# PCB-ETHMG-BOS2_v05-16.net
KiCad netlist of a schematic drawn in EAGLE
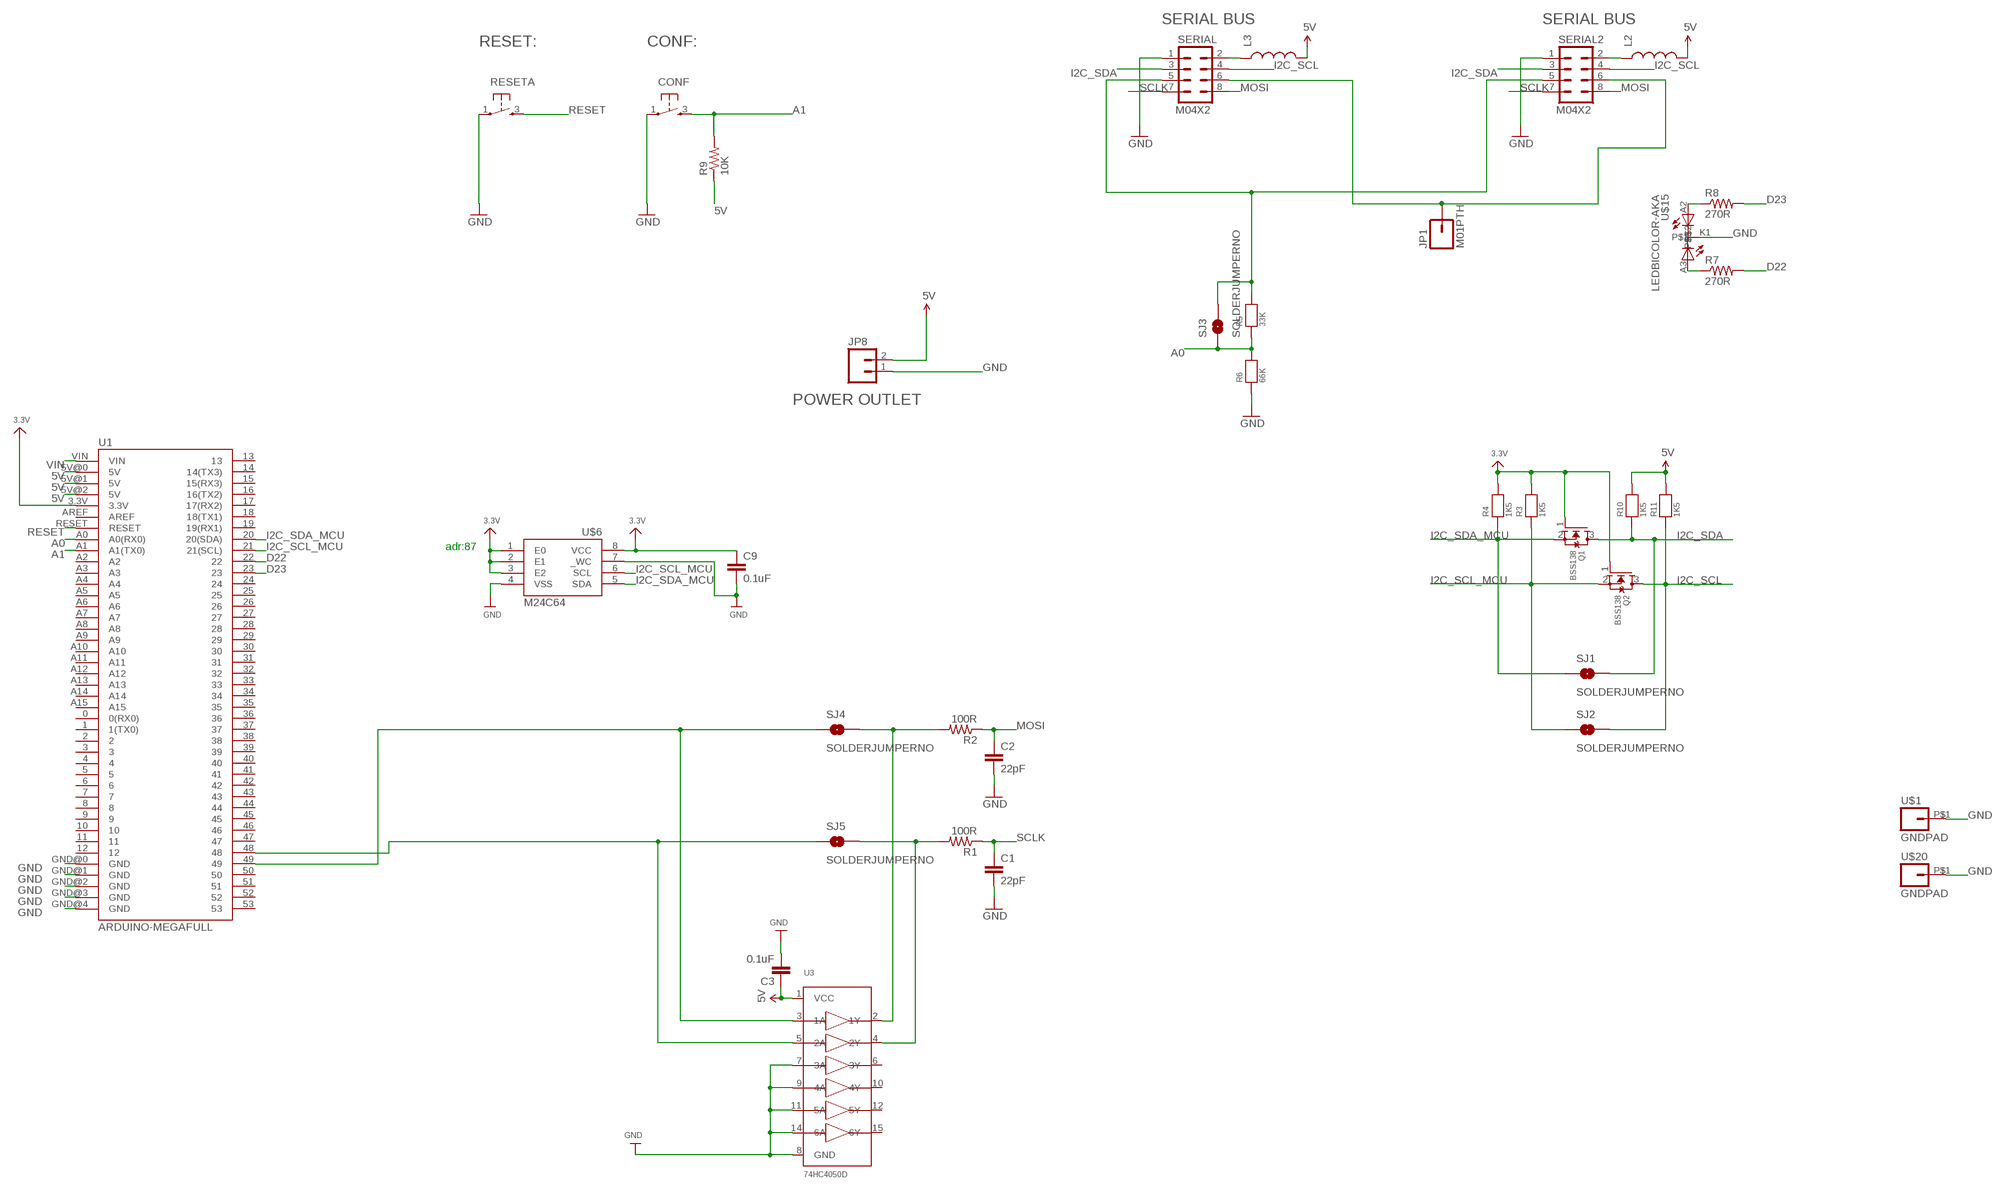
[diagram p0: schematic, sheet 1]

(export (version "E")
  (design (tool "Eeschema 10.0.6"))
  (components
    (comp (ref "C1")
      (value "22pF")
      (footprint "eagle-import:0603-CAP")
      (libsource (lib "eagle-import") (part "CAP0603-CAP"))
    )
    (comp (ref "C2")
      (value "22pF")
      (footprint "eagle-import:0603-CAP")
      (libsource (lib "eagle-import") (part "CAP0603-CAP"))
    )
    (comp (ref "C3")
      (value "0.1uF")
      (footprint "eagle-import:0603-CAP")
      (libsource (lib "eagle-import") (part "CAP0603-CAP"))
    )
    (comp (ref "C9")
      (value "0.1uF")
      (footprint "eagle-import:0603-CAP")
      (libsource (lib "eagle-import") (part "CAP0603-CAP"))
    )
    (comp (ref "CONF")
      (value "TAC_SWITCH")
      (footprint "eagle-import:PUSHBUTTON")
      (libsource (lib "eagle-import") (part "TAC_SWITCH"))
    )
    (comp (ref "JP1")
      (value "M01PTH")
      (footprint "eagle-import:1X01")
      (libsource (lib "eagle-import") (part "M01PTH"))
    )
    (comp (ref "JP8")
      (value "M02PTH4")
      (footprint "eagle-import:1X02_XTRA_BIG")
      (libsource (lib "eagle-import") (part "M02PTH4"))
    )
    (comp (ref "L2")
      (value "INDUCTOR0805")
      (footprint "eagle-import:0805")
      (libsource (lib "eagle-import") (part "INDUCTOR0805"))
    )
    (comp (ref "L3")
      (value "INDUCTOR0805")
      (footprint "eagle-import:0805")
      (libsource (lib "eagle-import") (part "INDUCTOR0805"))
    )
    (comp (ref "Q1")
      (value "BSS138")
      (footprint "eagle-import:SOT23-R")
      (libsource (lib "eagle-import") (part "MOSFET-NREFLOW"))
    )
    (comp (ref "Q2")
      (value "BSS138")
      (footprint "eagle-import:SOT23-R")
      (libsource (lib "eagle-import") (part "MOSFET-NREFLOW"))
    )
    (comp (ref "R1")
      (value "100R")
      (footprint "eagle-import:0603-RES")
      (libsource (lib "eagle-import") (part "RESISTOR0603-RES"))
    )
    (comp (ref "R2")
      (value "100R")
      (footprint "eagle-import:0603-RES")
      (libsource (lib "eagle-import") (part "RESISTOR0603-RES"))
    )
    (comp (ref "R3")
      (value "1K5")
      (footprint "eagle-import:0603")
      (libsource (lib "eagle-import") (part "RESISTOR0603"))
    )
    (comp (ref "R4")
      (value "1K5")
      (footprint "eagle-import:0603")
      (libsource (lib "eagle-import") (part "RESISTOR0603"))
    )
    (comp (ref "R5")
      (value "33K")
      (footprint "eagle-import:0603")
      (libsource (lib "eagle-import") (part "RESISTOR0603"))
    )
    (comp (ref "R6")
      (value "66K")
      (footprint "eagle-import:0603")
      (libsource (lib "eagle-import") (part "RESISTOR0603"))
    )
    (comp (ref "R7")
      (value "270R")
      (footprint "eagle-import:0603-RES")
      (libsource (lib "eagle-import") (part "RESISTOR0603-RES"))
    )
    (comp (ref "R8")
      (value "270R")
      (footprint "eagle-import:0603-RES")
      (libsource (lib "eagle-import") (part "RESISTOR0603-RES"))
    )
    (comp (ref "R9")
      (value "10K")
      (footprint "eagle-import:0603-RES")
      (libsource (lib "eagle-import") (part "RESISTOR0603-RES"))
    )
    (comp (ref "R10")
      (value "1K5")
      (footprint "eagle-import:0603")
      (libsource (lib "eagle-import") (part "RESISTOR0603"))
    )
    (comp (ref "R11")
      (value "1K5")
      (footprint "eagle-import:0603")
      (libsource (lib "eagle-import") (part "RESISTOR0603"))
    )
    (comp (ref "RESETA")
      (value "TAC_SWITCH")
      (footprint "eagle-import:PUSHBUTTON")
      (libsource (lib "eagle-import") (part "TAC_SWITCH"))
    )
    (comp (ref "SERIAL")
      (value "M04X2")
      (footprint "eagle-import:2X4")
      (libsource (lib "eagle-import") (part "M04X2"))
    )
    (comp (ref "SERIAL2")
      (value "M04X2")
      (footprint "eagle-import:2X4")
      (libsource (lib "eagle-import") (part "M04X2"))
    )
    (comp (ref "SJ1")
      (value "SOLDERJUMPERNO")
      (footprint "eagle-import:SJ_2S-NO")
      (libsource (lib "eagle-import") (part "SOLDERJUMPERNO"))
    )
    (comp (ref "SJ2")
      (value "SOLDERJUMPERNO")
      (footprint "eagle-import:SJ_2S-NO")
      (libsource (lib "eagle-import") (part "SOLDERJUMPERNO"))
    )
    (comp (ref "SJ3")
      (value "SOLDERJUMPERNO")
      (footprint "eagle-import:SJ_2S-NO")
      (libsource (lib "eagle-import") (part "SOLDERJUMPERNO"))
    )
    (comp (ref "SJ4")
      (value "SOLDERJUMPERNO")
      (footprint "eagle-import:SJ_2S-NO")
      (libsource (lib "eagle-import") (part "SOLDERJUMPERNO"))
    )
    (comp (ref "SJ5")
      (value "SOLDERJUMPERNO")
      (footprint "eagle-import:SJ_2S-NO")
      (libsource (lib "eagle-import") (part "SOLDERJUMPERNO"))
    )
    (comp (ref "U$1")
      (value "GNDPAD")
      (footprint "eagle-import:3.2MMPAD")
      (libsource (lib "eagle-import") (part "GNDPAD"))
    )
    (comp (ref "U$6")
      (value "M24C64")
      (footprint "eagle-import:TSSOP8")
      (libsource (lib "eagle-import") (part "M24C64"))
    )
    (comp (ref "U$15")
      (value "LEDBICOLOR-AKA")
      (footprint "eagle-import:LED5MM-BICOLOR")
      (libsource (lib "eagle-import") (part "LEDBICOLOR-AKA"))
    )
    (comp (ref "U$20")
      (value "GNDPAD")
      (footprint "eagle-import:3.2MMPAD")
      (libsource (lib "eagle-import") (part "GNDPAD"))
    )
    (comp (ref "U1")
      (value "ARDUINO-MEGAFULL")
      (footprint "eagle-import:ARDUINO_MEGA")
      (libsource (lib "eagle-import") (part "ARDUINO-MEGAFULL"))
    )
    (comp (ref "U3")
      (value "74HC4050D")
      (footprint "eagle-import:TSSOP16")
      (libsource (lib "eagle-import") (part "74HC4050DTSSOP16"))
    )
  )
  (nets
    (net (code "1") (name "/A0") (class "Default")
      (node (ref "R5") (pin "1") (pinfunction "1_1") (pintype "passive"))
      (node (ref "R6") (pin "2") (pinfunction "2_2") (pintype "passive"))
      (node (ref "SJ3") (pin "1") (pinfunction "1_1") (pintype "passive"))
      (node (ref "U1") (pin "A0") (pinfunction "A0(RX0)_A0") (pintype "bidirectional"))
    )
    (net (code "2") (name "/A1") (class "Default")
      (node (ref "CONF") (pin "3") (pinfunction "3_3") (pintype "passive"))
      (node (ref "R9") (pin "2") (pinfunction "2_2") (pintype "passive"))
      (node (ref "U1") (pin "A1") (pinfunction "A1(TX0)_A1") (pintype "bidirectional"))
    )
    (net (code "3") (name "/D22") (class "Default")
      (node (ref "R7") (pin "2") (pinfunction "2_2") (pintype "passive"))
      (node (ref "U1") (pin "22") (pinfunction "22_22") (pintype "bidirectional"))
    )
    (net (code "4") (name "/D23") (class "Default")
      (node (ref "R8") (pin "2") (pinfunction "2_2") (pintype "passive"))
      (node (ref "U1") (pin "23") (pinfunction "23_23") (pintype "bidirectional"))
    )
    (net (code "5") (name "/I2C_SCL") (class "Default")
      (node (ref "Q2") (pin "3") (pinfunction "D_3") (pintype "bidirectional"))
      (node (ref "R11") (pin "1") (pinfunction "1_1") (pintype "passive"))
      (node (ref "SERIAL") (pin "4") (pinfunction "4_4") (pintype "passive"))
      (node (ref "SERIAL2") (pin "4") (pinfunction "4_4") (pintype "passive"))
      (node (ref "SJ2") (pin "2") (pinfunction "2_2") (pintype "passive"))
    )
    (net (code "6") (name "/I2C_SCL_MCU") (class "Default")
      (node (ref "Q2") (pin "2") (pinfunction "S_2") (pintype "bidirectional"))
      (node (ref "R3") (pin "1") (pinfunction "1_1") (pintype "passive"))
      (node (ref "SJ2") (pin "1") (pinfunction "1_1") (pintype "passive"))
      (node (ref "U$6") (pin "6") (pinfunction "SCL_6") (pintype "bidirectional"))
      (node (ref "U1") (pin "21") (pinfunction "21(SCL)_21") (pintype "bidirectional"))
    )
    (net (code "7") (name "/I2C_SDA") (class "Default")
      (node (ref "Q1") (pin "3") (pinfunction "D_3") (pintype "bidirectional"))
      (node (ref "R10") (pin "1") (pinfunction "1_1") (pintype "passive"))
      (node (ref "SERIAL") (pin "3") (pinfunction "3_3") (pintype "passive"))
      (node (ref "SERIAL2") (pin "3") (pinfunction "3_3") (pintype "passive"))
      (node (ref "SJ1") (pin "2") (pinfunction "2_2") (pintype "passive"))
    )
    (net (code "8") (name "/I2C_SDA_MCU") (class "Default")
      (node (ref "Q1") (pin "2") (pinfunction "S_2") (pintype "bidirectional"))
      (node (ref "R4") (pin "1") (pinfunction "1_1") (pintype "passive"))
      (node (ref "SJ1") (pin "1") (pinfunction "1_1") (pintype "passive"))
      (node (ref "U$6") (pin "5") (pinfunction "SDA_5") (pintype "bidirectional"))
      (node (ref "U1") (pin "20") (pinfunction "20(SDA)_20") (pintype "bidirectional"))
    )
    (net (code "9") (name "/MOSI") (class "Default")
      (node (ref "C2") (pin "1") (pinfunction "1_1") (pintype "passive"))
      (node (ref "R2") (pin "1") (pinfunction "1_1") (pintype "passive"))
      (node (ref "SERIAL") (pin "8") (pinfunction "8_8") (pintype "passive"))
      (node (ref "SERIAL2") (pin "8") (pinfunction "8_8") (pintype "passive"))
    )
    (net (code "10") (name "/RESET") (class "Default")
      (node (ref "RESETA") (pin "3") (pinfunction "3_3") (pintype "passive"))
      (node (ref "U1") (pin "RESET") (pinfunction "RESET_RESET") (pintype "bidirectional"))
    )
    (net (code "11") (name "/SCLK") (class "Default")
      (node (ref "C1") (pin "1") (pinfunction "1_1") (pintype "passive"))
      (node (ref "R1") (pin "1") (pinfunction "1_1") (pintype "passive"))
      (node (ref "SERIAL") (pin "7") (pinfunction "7_7") (pintype "passive"))
      (node (ref "SERIAL2") (pin "7") (pinfunction "7_7") (pintype "passive"))
    )
    (net (code "12") (name "/VIN") (class "Default")
      (node (ref "U1") (pin "VIN") (pinfunction "VIN_VIN") (pintype "bidirectional"))
    )
    (net (code "13") (name "3.3V") (class "Default")
      (node (ref "C9") (pin "1") (pinfunction "1_1") (pintype "passive"))
      (node (ref "Q1") (pin "1") (pinfunction "G_1") (pintype "bidirectional"))
      (node (ref "Q2") (pin "1") (pinfunction "G_1") (pintype "bidirectional"))
      (node (ref "R3") (pin "2") (pinfunction "2_2") (pintype "passive"))
      (node (ref "R4") (pin "2") (pinfunction "2_2") (pintype "passive"))
      (node (ref "U$6") (pin "1") (pinfunction "E0_1") (pintype "bidirectional"))
      (node (ref "U$6") (pin "2") (pinfunction "E1_2") (pintype "bidirectional"))
      (node (ref "U$6") (pin "3") (pinfunction "E2_3") (pintype "bidirectional"))
      (node (ref "U$6") (pin "8") (pinfunction "VCC_8") (pintype "power_in"))
      (node (ref "U1") (pin "3.3V") (pinfunction "3.3V_3.3V") (pintype "bidirectional"))
    )
    (net (code "14") (name "5V") (class "Default")
      (node (ref "C3") (pin "1") (pinfunction "1_1") (pintype "passive"))
      (node (ref "JP8") (pin "2") (pinfunction "2_2") (pintype "passive"))
      (node (ref "L2") (pin "2") (pinfunction "2_2") (pintype "passive"))
      (node (ref "L3") (pin "2") (pinfunction "2_2") (pintype "passive"))
      (node (ref "R10") (pin "2") (pinfunction "2_2") (pintype "passive"))
      (node (ref "R11") (pin "2") (pinfunction "2_2") (pintype "passive"))
      (node (ref "R9") (pin "1") (pinfunction "1_1") (pintype "passive"))
      (node (ref "U1") (pin "5V@0") (pinfunction "5V_5V@0") (pintype "bidirectional"))
      (node (ref "U1") (pin "5V@1") (pinfunction "5V_5V@1") (pintype "bidirectional"))
      (node (ref "U1") (pin "5V@2") (pinfunction "5V_5V@2") (pintype "bidirectional"))
      (node (ref "U3") (pin "1") (pinfunction "VCC_1") (pintype "bidirectional"))
    )
    (net (code "15") (name "GND") (class "Default")
      (node (ref "C1") (pin "2") (pinfunction "2_2") (pintype "passive"))
      (node (ref "C2") (pin "2") (pinfunction "2_2") (pintype "passive"))
      (node (ref "C3") (pin "2") (pinfunction "2_2") (pintype "passive"))
      (node (ref "C9") (pin "2") (pinfunction "2_2") (pintype "passive"))
      (node (ref "CONF") (pin "1") (pinfunction "1_1") (pintype "passive"))
      (node (ref "JP8") (pin "1") (pinfunction "1_1") (pintype "passive"))
      (node (ref "R6") (pin "1") (pinfunction "1_1") (pintype "passive"))
      (node (ref "RESETA") (pin "1") (pinfunction "1_1") (pintype "passive"))
      (node (ref "SERIAL") (pin "1") (pinfunction "1_1") (pintype "passive"))
      (node (ref "SERIAL2") (pin "1") (pinfunction "1_1") (pintype "passive"))
      (node (ref "U$1") (pin "P$1") (pinfunction "1_P$1") (pintype "passive"))
      (node (ref "U$15") (pin "K1") (pinfunction "P$1_K1") (pintype "bidirectional"))
      (node (ref "U$20") (pin "P$1") (pinfunction "1_P$1") (pintype "passive"))
      (node (ref "U$6") (pin "4") (pinfunction "VSS_4") (pintype "power_in"))
      (node (ref "U$6") (pin "7") (pinfunction "_WC_7") (pintype "bidirectional"))
      (node (ref "U1") (pin "GND@0") (pinfunction "GND_GND@0") (pintype "bidirectional"))
      (node (ref "U1") (pin "GND@1") (pinfunction "GND_GND@1") (pintype "bidirectional"))
      (node (ref "U1") (pin "GND@2") (pinfunction "GND_GND@2") (pintype "bidirectional"))
      (node (ref "U1") (pin "GND@3") (pinfunction "GND_GND@3") (pintype "bidirectional"))
      (node (ref "U1") (pin "GND@4") (pinfunction "GND_GND@4") (pintype "bidirectional"))
      (node (ref "U3") (pin "11") (pinfunction "5A_11") (pintype "bidirectional"))
      (node (ref "U3") (pin "14") (pinfunction "6A_14") (pintype "bidirectional"))
      (node (ref "U3") (pin "7") (pinfunction "3A_7") (pintype "bidirectional"))
      (node (ref "U3") (pin "8") (pinfunction "GND_8") (pintype "bidirectional"))
      (node (ref "U3") (pin "9") (pinfunction "4A_9") (pintype "bidirectional"))
    )
    (net (code "16") (name "Net-(JP1-Pad1)") (class "Default")
      (node (ref "JP1") (pin "1") (pinfunction "1_1") (pintype "passive"))
      (node (ref "SERIAL") (pin "6") (pinfunction "6_6") (pintype "passive"))
      (node (ref "SERIAL2") (pin "6") (pinfunction "6_6") (pintype "passive"))
    )
    (net (code "17") (name "Net-(L2-Pad1)") (class "Default")
      (node (ref "L2") (pin "1") (pinfunction "1_1") (pintype "passive"))
      (node (ref "SERIAL2") (pin "2") (pinfunction "2_2") (pintype "passive"))
    )
    (net (code "18") (name "Net-(L3-Pad1)") (class "Default")
      (node (ref "L3") (pin "1") (pinfunction "1_1") (pintype "passive"))
      (node (ref "SERIAL") (pin "2") (pinfunction "2_2") (pintype "passive"))
    )
    (net (code "19") (name "Net-(R5-Pad2)") (class "Default")
      (node (ref "R5") (pin "2") (pinfunction "2_2") (pintype "passive"))
      (node (ref "SERIAL") (pin "5") (pinfunction "5_5") (pintype "passive"))
      (node (ref "SERIAL2") (pin "5") (pinfunction "5_5") (pintype "passive"))
      (node (ref "SJ3") (pin "2") (pinfunction "2_2") (pintype "passive"))
    )
    (net (code "20") (name "Net-(U$15-P$2)") (class "Default")
      (node (ref "R8") (pin "1") (pinfunction "1_1") (pintype "passive"))
      (node (ref "U$15") (pin "A2") (pinfunction "P$2_A2") (pintype "bidirectional"))
    )
    (net (code "21") (name "Net-(U$15-P$3)") (class "Default")
      (node (ref "R7") (pin "1") (pinfunction "1_1") (pintype "passive"))
      (node (ref "U$15") (pin "A3") (pinfunction "P$3_A3") (pintype "bidirectional"))
    )
    (net (code "22") (name "Net-(U3-1A)") (class "Default")
      (node (ref "SJ4") (pin "1") (pinfunction "1_1") (pintype "passive"))
      (node (ref "U1") (pin "49") (pinfunction "49_49") (pintype "bidirectional"))
      (node (ref "U3") (pin "3") (pinfunction "1A_3") (pintype "bidirectional"))
    )
    (net (code "23") (name "Net-(U3-1Y)") (class "Default")
      (node (ref "R2") (pin "2") (pinfunction "2_2") (pintype "passive"))
      (node (ref "SJ4") (pin "2") (pinfunction "2_2") (pintype "passive"))
      (node (ref "U3") (pin "2") (pinfunction "1Y_2") (pintype "bidirectional"))
    )
    (net (code "24") (name "Net-(U3-2A)") (class "Default")
      (node (ref "SJ5") (pin "1") (pinfunction "1_1") (pintype "passive"))
      (node (ref "U1") (pin "48") (pinfunction "48_48") (pintype "bidirectional"))
      (node (ref "U3") (pin "5") (pinfunction "2A_5") (pintype "bidirectional"))
    )
    (net (code "25") (name "Net-(U3-2Y)") (class "Default")
      (node (ref "R1") (pin "2") (pinfunction "2_2") (pintype "passive"))
      (node (ref "SJ5") (pin "2") (pinfunction "2_2") (pintype "passive"))
      (node (ref "U3") (pin "4") (pinfunction "2Y_4") (pintype "bidirectional"))
    )
    (net (code "26") (name "unconnected-(U1-0(RX0)-Pad0)") (class "Default")
      (node (ref "U1") (pin "0") (pinfunction "0(RX0)_0") (pintype "bidirectional"))
    )
    (net (code "27") (name "unconnected-(U1-1(TX0)-Pad1)") (class "Default")
      (node (ref "U1") (pin "1") (pinfunction "1(TX0)_1") (pintype "bidirectional"))
    )
    (net (code "28") (name "unconnected-(U1-14(TX3)-Pad14)") (class "Default")
      (node (ref "U1") (pin "14") (pinfunction "14(TX3)_14") (pintype "bidirectional"))
    )
    (net (code "29") (name "unconnected-(U1-15(RX3)-Pad15)") (class "Default")
      (node (ref "U1") (pin "15") (pinfunction "15(RX3)_15") (pintype "bidirectional"))
    )
    (net (code "30") (name "unconnected-(U1-16(TX2)-Pad16)") (class "Default")
      (node (ref "U1") (pin "16") (pinfunction "16(TX2)_16") (pintype "bidirectional"))
    )
    (net (code "31") (name "unconnected-(U1-17(RX2)-Pad17)") (class "Default")
      (node (ref "U1") (pin "17") (pinfunction "17(RX2)_17") (pintype "bidirectional"))
    )
    (net (code "32") (name "unconnected-(U1-18(TX1)-Pad18)") (class "Default")
      (node (ref "U1") (pin "18") (pinfunction "18(TX1)_18") (pintype "bidirectional"))
    )
    (net (code "33") (name "unconnected-(U1-19(RX1)-Pad19)") (class "Default")
      (node (ref "U1") (pin "19") (pinfunction "19(RX1)_19") (pintype "bidirectional"))
    )
    (net (code "34") (name "unconnected-(U1-Pad2)") (class "Default")
      (node (ref "U1") (pin "2") (pinfunction "2_2") (pintype "bidirectional"))
    )
    (net (code "35") (name "unconnected-(U1-Pad3)") (class "Default")
      (node (ref "U1") (pin "3") (pinfunction "3_3") (pintype "bidirectional"))
    )
    (net (code "36") (name "unconnected-(U1-Pad4)") (class "Default")
      (node (ref "U1") (pin "4") (pinfunction "4_4") (pintype "bidirectional"))
    )
    (net (code "37") (name "unconnected-(U1-Pad5)") (class "Default")
      (node (ref "U1") (pin "5") (pinfunction "5_5") (pintype "bidirectional"))
    )
    (net (code "38") (name "unconnected-(U1-Pad6)") (class "Default")
      (node (ref "U1") (pin "6") (pinfunction "6_6") (pintype "bidirectional"))
    )
    (net (code "39") (name "unconnected-(U1-Pad7)") (class "Default")
      (node (ref "U1") (pin "7") (pinfunction "7_7") (pintype "bidirectional"))
    )
    (net (code "40") (name "unconnected-(U1-Pad8)") (class "Default")
      (node (ref "U1") (pin "8") (pinfunction "8_8") (pintype "bidirectional"))
    )
    (net (code "41") (name "unconnected-(U1-Pad9)") (class "Default")
      (node (ref "U1") (pin "9") (pinfunction "9_9") (pintype "bidirectional"))
    )
    (net (code "42") (name "unconnected-(U1-Pad10)") (class "Default")
      (node (ref "U1") (pin "10") (pinfunction "10_10") (pintype "bidirectional"))
    )
    (net (code "43") (name "unconnected-(U1-Pad11)") (class "Default")
      (node (ref "U1") (pin "11") (pinfunction "11_11") (pintype "bidirectional"))
    )
    (net (code "44") (name "unconnected-(U1-Pad12)") (class "Default")
      (node (ref "U1") (pin "12") (pinfunction "12_12") (pintype "bidirectional"))
    )
    (net (code "45") (name "unconnected-(U1-Pad13)") (class "Default")
      (node (ref "U1") (pin "13") (pinfunction "13_13") (pintype "bidirectional"))
    )
    (net (code "46") (name "unconnected-(U1-Pad24)") (class "Default")
      (node (ref "U1") (pin "24") (pinfunction "24_24") (pintype "bidirectional"))
    )
    (net (code "47") (name "unconnected-(U1-Pad25)") (class "Default")
      (node (ref "U1") (pin "25") (pinfunction "25_25") (pintype "bidirectional"))
    )
    (net (code "48") (name "unconnected-(U1-Pad26)") (class "Default")
      (node (ref "U1") (pin "26") (pinfunction "26_26") (pintype "bidirectional"))
    )
    (net (code "49") (name "unconnected-(U1-Pad27)") (class "Default")
      (node (ref "U1") (pin "27") (pinfunction "27_27") (pintype "bidirectional"))
    )
    (net (code "50") (name "unconnected-(U1-Pad28)") (class "Default")
      (node (ref "U1") (pin "28") (pinfunction "28_28") (pintype "bidirectional"))
    )
    (net (code "51") (name "unconnected-(U1-Pad29)") (class "Default")
      (node (ref "U1") (pin "29") (pinfunction "29_29") (pintype "bidirectional"))
    )
    (net (code "52") (name "unconnected-(U1-Pad30)") (class "Default")
      (node (ref "U1") (pin "30") (pinfunction "30_30") (pintype "bidirectional"))
    )
    (net (code "53") (name "unconnected-(U1-Pad31)") (class "Default")
      (node (ref "U1") (pin "31") (pinfunction "31_31") (pintype "bidirectional"))
    )
    (net (code "54") (name "unconnected-(U1-Pad32)") (class "Default")
      (node (ref "U1") (pin "32") (pinfunction "32_32") (pintype "bidirectional"))
    )
    (net (code "55") (name "unconnected-(U1-Pad33)") (class "Default")
      (node (ref "U1") (pin "33") (pinfunction "33_33") (pintype "bidirectional"))
    )
    (net (code "56") (name "unconnected-(U1-Pad34)") (class "Default")
      (node (ref "U1") (pin "34") (pinfunction "34_34") (pintype "bidirectional"))
    )
    (net (code "57") (name "unconnected-(U1-Pad35)") (class "Default")
      (node (ref "U1") (pin "35") (pinfunction "35_35") (pintype "bidirectional"))
    )
    (net (code "58") (name "unconnected-(U1-Pad36)") (class "Default")
      (node (ref "U1") (pin "36") (pinfunction "36_36") (pintype "bidirectional"))
    )
    (net (code "59") (name "unconnected-(U1-Pad37)") (class "Default")
      (node (ref "U1") (pin "37") (pinfunction "37_37") (pintype "bidirectional"))
    )
    (net (code "60") (name "unconnected-(U1-Pad38)") (class "Default")
      (node (ref "U1") (pin "38") (pinfunction "38_38") (pintype "bidirectional"))
    )
    (net (code "61") (name "unconnected-(U1-Pad39)") (class "Default")
      (node (ref "U1") (pin "39") (pinfunction "39_39") (pintype "bidirectional"))
    )
    (net (code "62") (name "unconnected-(U1-Pad40)") (class "Default")
      (node (ref "U1") (pin "40") (pinfunction "40_40") (pintype "bidirectional"))
    )
    (net (code "63") (name "unconnected-(U1-Pad41)") (class "Default")
      (node (ref "U1") (pin "41") (pinfunction "41_41") (pintype "bidirectional"))
    )
    (net (code "64") (name "unconnected-(U1-Pad42)") (class "Default")
      (node (ref "U1") (pin "42") (pinfunction "42_42") (pintype "bidirectional"))
    )
    (net (code "65") (name "unconnected-(U1-Pad43)") (class "Default")
      (node (ref "U1") (pin "43") (pinfunction "43_43") (pintype "bidirectional"))
    )
    (net (code "66") (name "unconnected-(U1-Pad44)") (class "Default")
      (node (ref "U1") (pin "44") (pinfunction "44_44") (pintype "bidirectional"))
    )
    (net (code "67") (name "unconnected-(U1-Pad45)") (class "Default")
      (node (ref "U1") (pin "45") (pinfunction "45_45") (pintype "bidirectional"))
    )
    (net (code "68") (name "unconnected-(U1-Pad46)") (class "Default")
      (node (ref "U1") (pin "46") (pinfunction "46_46") (pintype "bidirectional"))
    )
    (net (code "69") (name "unconnected-(U1-Pad47)") (class "Default")
      (node (ref "U1") (pin "47") (pinfunction "47_47") (pintype "bidirectional"))
    )
    (net (code "70") (name "unconnected-(U1-Pad50)") (class "Default")
      (node (ref "U1") (pin "50") (pinfunction "50_50") (pintype "bidirectional"))
    )
    (net (code "71") (name "unconnected-(U1-Pad51)") (class "Default")
      (node (ref "U1") (pin "51") (pinfunction "51_51") (pintype "bidirectional"))
    )
    (net (code "72") (name "unconnected-(U1-Pad52)") (class "Default")
      (node (ref "U1") (pin "52") (pinfunction "52_52") (pintype "bidirectional"))
    )
    (net (code "73") (name "unconnected-(U1-Pad53)") (class "Default")
      (node (ref "U1") (pin "53") (pinfunction "53_53") (pintype "bidirectional"))
    )
    (net (code "74") (name "unconnected-(U1-PadA2)") (class "Default")
      (node (ref "U1") (pin "A2") (pinfunction "A2_A2") (pintype "bidirectional"))
    )
    (net (code "75") (name "unconnected-(U1-PadA3)") (class "Default")
      (node (ref "U1") (pin "A3") (pinfunction "A3_A3") (pintype "bidirectional"))
    )
    (net (code "76") (name "unconnected-(U1-PadA4)") (class "Default")
      (node (ref "U1") (pin "A4") (pinfunction "A4_A4") (pintype "bidirectional"))
    )
    (net (code "77") (name "unconnected-(U1-PadA5)") (class "Default")
      (node (ref "U1") (pin "A5") (pinfunction "A5_A5") (pintype "bidirectional"))
    )
    (net (code "78") (name "unconnected-(U1-PadA6)") (class "Default")
      (node (ref "U1") (pin "A6") (pinfunction "A6_A6") (pintype "bidirectional"))
    )
    (net (code "79") (name "unconnected-(U1-PadA7)") (class "Default")
      (node (ref "U1") (pin "A7") (pinfunction "A7_A7") (pintype "bidirectional"))
    )
    (net (code "80") (name "unconnected-(U1-PadA8)") (class "Default")
      (node (ref "U1") (pin "A8") (pinfunction "A8_A8") (pintype "bidirectional"))
    )
    (net (code "81") (name "unconnected-(U1-PadA9)") (class "Default")
      (node (ref "U1") (pin "A9") (pinfunction "A9_A9") (pintype "bidirectional"))
    )
    (net (code "82") (name "unconnected-(U1-PadA10)") (class "Default")
      (node (ref "U1") (pin "A10") (pinfunction "A10_A10") (pintype "bidirectional"))
    )
    (net (code "83") (name "unconnected-(U1-PadA11)") (class "Default")
      (node (ref "U1") (pin "A11") (pinfunction "A11_A11") (pintype "bidirectional"))
    )
    (net (code "84") (name "unconnected-(U1-PadA12)") (class "Default")
      (node (ref "U1") (pin "A12") (pinfunction "A12_A12") (pintype "bidirectional"))
    )
    (net (code "85") (name "unconnected-(U1-PadA13)") (class "Default")
      (node (ref "U1") (pin "A13") (pinfunction "A13_A13") (pintype "bidirectional"))
    )
    (net (code "86") (name "unconnected-(U1-PadA14)") (class "Default")
      (node (ref "U1") (pin "A14") (pinfunction "A14_A14") (pintype "bidirectional"))
    )
    (net (code "87") (name "unconnected-(U1-PadA15)") (class "Default")
      (node (ref "U1") (pin "A15") (pinfunction "A15_A15") (pintype "bidirectional"))
    )
    (net (code "88") (name "unconnected-(U1-PadAREF)") (class "Default")
      (node (ref "U1") (pin "AREF") (pinfunction "AREF_AREF") (pintype "bidirectional"))
    )
    (net (code "89") (name "unconnected-(U3-3Y-Pad6)") (class "Default")
      (node (ref "U3") (pin "6") (pinfunction "3Y_6") (pintype "bidirectional"))
    )
    (net (code "90") (name "unconnected-(U3-4Y-Pad10)") (class "Default")
      (node (ref "U3") (pin "10") (pinfunction "4Y_10") (pintype "bidirectional"))
    )
    (net (code "91") (name "unconnected-(U3-5Y-Pad12)") (class "Default")
      (node (ref "U3") (pin "12") (pinfunction "5Y_12") (pintype "bidirectional"))
    )
    (net (code "92") (name "unconnected-(U3-6Y-Pad15)") (class "Default")
      (node (ref "U3") (pin "15") (pinfunction "6Y_15") (pintype "bidirectional"))
    )
  )
)
